# traffic_signals.net
KiCad netlist of a schematic drawn in EAGLE
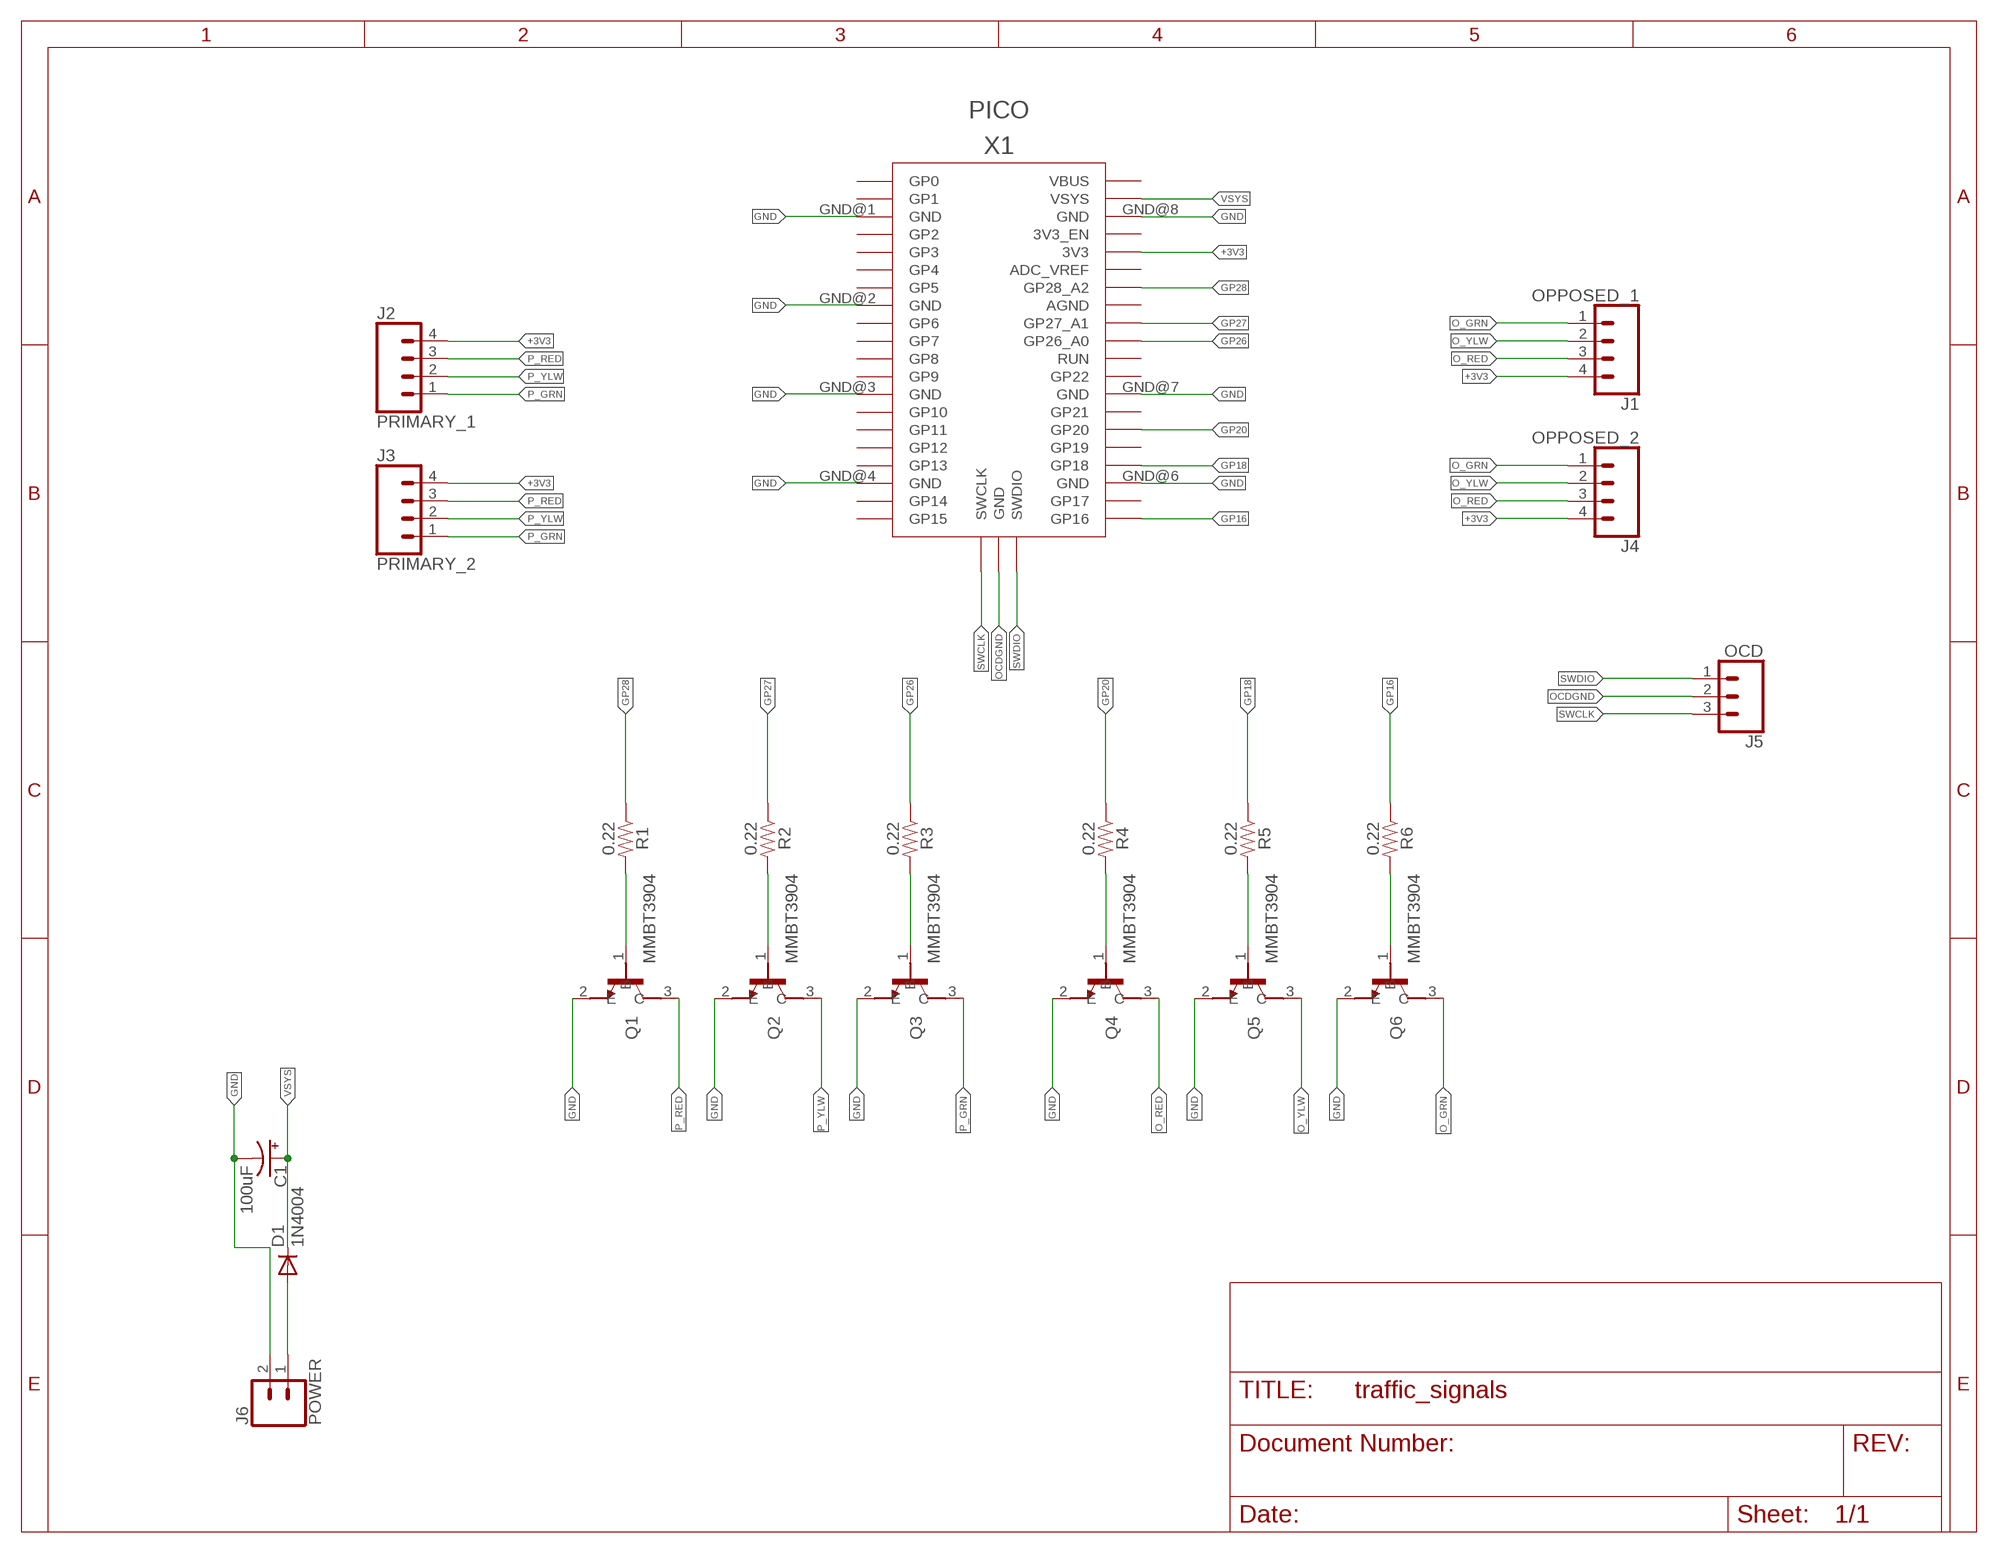
[diagram p0: schematic, sheet 1]

(export (version "E")
  (design (tool "Eeschema 10.0.6"))
  (components
    (comp (ref "C1")
      (value "100uF")
      (footprint "eagle-import:CPOL-RADIAL-2.5MM-6.5MM")
      (libsource (lib "eagle-import") (part "100UF-POLAR-RADIAL-2.5MM-25V-20%"))
    )
    (comp (ref "D1")
      (value "1N4004")
      (footprint "eagle-import:DO41-10")
      (libsource (lib "eagle-import") (part "1N4004"))
    )
    (comp (ref "J1")
      (value "OPPOSED_1")
      (footprint "eagle-import:1X04")
      (libsource (lib "eagle-import") (part "CONN_04"))
    )
    (comp (ref "J2")
      (value "PRIMARY_1")
      (footprint "eagle-import:1X04")
      (libsource (lib "eagle-import") (part "CONN_04"))
    )
    (comp (ref "J3")
      (value "PRIMARY_2")
      (footprint "eagle-import:1X04")
      (libsource (lib "eagle-import") (part "CONN_04"))
    )
    (comp (ref "J4")
      (value "OPPOSED_2")
      (footprint "eagle-import:1X04")
      (libsource (lib "eagle-import") (part "CONN_04"))
    )
    (comp (ref "J5")
      (value "OCD")
      (footprint "eagle-import:1X03")
      (libsource (lib "eagle-import") (part "CONN_03"))
    )
    (comp (ref "J6")
      (value "POWER")
      (footprint "eagle-import:1X02")
      (libsource (lib "eagle-import") (part "CONN_02"))
    )
    (comp (ref "Q1")
      (value "MMBT3904")
      (footprint "eagle-import:SOT95P240X120-3N")
      (fields (field (name "MF") "STMicroelectronics"))
      (libsource (lib "eagle-import") (part "MMBT3904"))
    )
    (comp (ref "Q2")
      (value "MMBT3904")
      (footprint "eagle-import:SOT95P240X120-3N")
      (fields (field (name "MF") "STMicroelectronics"))
      (libsource (lib "eagle-import") (part "MMBT3904"))
    )
    (comp (ref "Q3")
      (value "MMBT3904")
      (footprint "eagle-import:SOT95P240X120-3N")
      (fields (field (name "MF") "STMicroelectronics"))
      (libsource (lib "eagle-import") (part "MMBT3904"))
    )
    (comp (ref "Q4")
      (value "MMBT3904")
      (footprint "eagle-import:SOT95P240X120-3N")
      (fields (field (name "MF") "STMicroelectronics"))
      (libsource (lib "eagle-import") (part "MMBT3904"))
    )
    (comp (ref "Q5")
      (value "MMBT3904")
      (footprint "eagle-import:SOT95P240X120-3N")
      (fields (field (name "MF") "STMicroelectronics"))
      (libsource (lib "eagle-import") (part "MMBT3904"))
    )
    (comp (ref "Q6")
      (value "MMBT3904")
      (footprint "eagle-import:SOT95P240X120-3N")
      (fields (field (name "MF") "STMicroelectronics"))
      (libsource (lib "eagle-import") (part "MMBT3904"))
    )
    (comp (ref "R1")
      (value "0.22")
      (footprint "eagle-import:0805")
      (libsource (lib "eagle-import") (part "0.22OHM-0805-1/4W-1%"))
    )
    (comp (ref "R2")
      (value "0.22")
      (footprint "eagle-import:0805")
      (libsource (lib "eagle-import") (part "0.22OHM-0805-1/4W-1%"))
    )
    (comp (ref "R3")
      (value "0.22")
      (footprint "eagle-import:0805")
      (libsource (lib "eagle-import") (part "0.22OHM-0805-1/4W-1%"))
    )
    (comp (ref "R4")
      (value "0.22")
      (footprint "eagle-import:0805")
      (libsource (lib "eagle-import") (part "0.22OHM-0805-1/4W-1%"))
    )
    (comp (ref "R5")
      (value "0.22")
      (footprint "eagle-import:0805")
      (libsource (lib "eagle-import") (part "0.22OHM-0805-1/4W-1%"))
    )
    (comp (ref "R6")
      (value "0.22")
      (footprint "eagle-import:0805")
      (libsource (lib "eagle-import") (part "0.22OHM-0805-1/4W-1%"))
    )
    (comp (ref "X1")
      (value "PICO")
      (footprint "eagle-import:RPI_PICO_TH")
      (libsource (lib "eagle-import") (part "RPI_PICO_IG-TH"))
    )
  )
  (nets
    (net (code "1") (name "+3V3") (class "Default")
      (node (ref "J1") (pin "4") (pinfunction "4_4") (pintype "passive"))
      (node (ref "J2") (pin "4") (pinfunction "4_4") (pintype "passive"))
      (node (ref "J3") (pin "4") (pinfunction "4_4") (pintype "passive"))
      (node (ref "J4") (pin "4") (pinfunction "4_4") (pintype "passive"))
      (node (ref "X1") (pin "3V3") (pinfunction "3V3_3V3") (pintype "bidirectional"))
    )
    (net (code "2") (name "GND") (class "Default")
      (node (ref "C1") (pin "2") (pinfunction "-_2") (pintype "passive"))
      (node (ref "J6") (pin "2") (pinfunction "2_2") (pintype "passive"))
      (node (ref "Q1") (pin "2") (pinfunction "E_2") (pintype "passive"))
      (node (ref "Q2") (pin "2") (pinfunction "E_2") (pintype "passive"))
      (node (ref "Q3") (pin "2") (pinfunction "E_2") (pintype "passive"))
      (node (ref "Q4") (pin "2") (pinfunction "E_2") (pintype "passive"))
      (node (ref "Q5") (pin "2") (pinfunction "E_2") (pintype "passive"))
      (node (ref "Q6") (pin "2") (pinfunction "E_2") (pintype "passive"))
      (node (ref "X1") (pin "GND@1") (pinfunction "GND_GND@1") (pintype "bidirectional"))
      (node (ref "X1") (pin "GND@2") (pinfunction "GND_GND@2") (pintype "bidirectional"))
      (node (ref "X1") (pin "GND@3") (pinfunction "GND_GND@3") (pintype "bidirectional"))
      (node (ref "X1") (pin "GND@4") (pinfunction "GND_GND@4") (pintype "bidirectional"))
      (node (ref "X1") (pin "GND@6") (pinfunction "GND_GND@6") (pintype "bidirectional"))
      (node (ref "X1") (pin "GND@7") (pinfunction "GND_GND@7") (pintype "bidirectional"))
      (node (ref "X1") (pin "GND@8") (pinfunction "GND_GND@8") (pintype "bidirectional"))
    )
    (net (code "3") (name "GP16") (class "Default")
      (node (ref "R6") (pin "1") (pinfunction "1_1") (pintype "passive"))
      (node (ref "X1") (pin "GP16") (pinfunction "GP16_GP16") (pintype "bidirectional"))
    )
    (net (code "4") (name "GP18") (class "Default")
      (node (ref "R5") (pin "1") (pinfunction "1_1") (pintype "passive"))
      (node (ref "X1") (pin "GP18") (pinfunction "GP18_GP18") (pintype "bidirectional"))
    )
    (net (code "5") (name "GP20") (class "Default")
      (node (ref "R4") (pin "1") (pinfunction "1_1") (pintype "passive"))
      (node (ref "X1") (pin "GP20") (pinfunction "GP20_GP20") (pintype "bidirectional"))
    )
    (net (code "6") (name "GP26") (class "Default")
      (node (ref "R3") (pin "1") (pinfunction "1_1") (pintype "passive"))
      (node (ref "X1") (pin "GP26_A0") (pinfunction "GP26_A0_GP26_A0") (pintype "bidirectional"))
    )
    (net (code "7") (name "GP27") (class "Default")
      (node (ref "R2") (pin "1") (pinfunction "1_1") (pintype "passive"))
      (node (ref "X1") (pin "GP27_A1") (pinfunction "GP27_A1_GP27_A1") (pintype "bidirectional"))
    )
    (net (code "8") (name "GP28") (class "Default")
      (node (ref "R1") (pin "1") (pinfunction "1_1") (pintype "passive"))
      (node (ref "X1") (pin "GP28_A2") (pinfunction "GP28_A2_GP28_A2") (pintype "bidirectional"))
    )
    (net (code "9") (name "Net-(D1-PadA)") (class "Default")
      (node (ref "D1") (pin "A") (pinfunction "A_A") (pintype "passive"))
      (node (ref "J6") (pin "1") (pinfunction "1_1") (pintype "passive"))
    )
    (net (code "10") (name "Net-(Q1-B)") (class "Default")
      (node (ref "Q1") (pin "1") (pinfunction "B_1") (pintype "passive"))
      (node (ref "R1") (pin "2") (pinfunction "2_2") (pintype "passive"))
    )
    (net (code "11") (name "Net-(Q2-B)") (class "Default")
      (node (ref "Q2") (pin "1") (pinfunction "B_1") (pintype "passive"))
      (node (ref "R2") (pin "2") (pinfunction "2_2") (pintype "passive"))
    )
    (net (code "12") (name "Net-(Q3-B)") (class "Default")
      (node (ref "Q3") (pin "1") (pinfunction "B_1") (pintype "passive"))
      (node (ref "R3") (pin "2") (pinfunction "2_2") (pintype "passive"))
    )
    (net (code "13") (name "Net-(Q4-B)") (class "Default")
      (node (ref "Q4") (pin "1") (pinfunction "B_1") (pintype "passive"))
      (node (ref "R4") (pin "2") (pinfunction "2_2") (pintype "passive"))
    )
    (net (code "14") (name "Net-(Q5-B)") (class "Default")
      (node (ref "Q5") (pin "1") (pinfunction "B_1") (pintype "passive"))
      (node (ref "R5") (pin "2") (pinfunction "2_2") (pintype "passive"))
    )
    (net (code "15") (name "Net-(Q6-B)") (class "Default")
      (node (ref "Q6") (pin "1") (pinfunction "B_1") (pintype "passive"))
      (node (ref "R6") (pin "2") (pinfunction "2_2") (pintype "passive"))
    )
    (net (code "16") (name "OCDGND") (class "Default")
      (node (ref "J5") (pin "2") (pinfunction "2_2") (pintype "passive"))
      (node (ref "X1") (pin "GND@5") (pinfunction "GND_GND@5") (pintype "bidirectional"))
    )
    (net (code "17") (name "O_GRN") (class "Default")
      (node (ref "J1") (pin "1") (pinfunction "1_1") (pintype "passive"))
      (node (ref "J4") (pin "1") (pinfunction "1_1") (pintype "passive"))
      (node (ref "Q6") (pin "3") (pinfunction "C_3") (pintype "passive"))
    )
    (net (code "18") (name "O_RED") (class "Default")
      (node (ref "J1") (pin "3") (pinfunction "3_3") (pintype "passive"))
      (node (ref "J4") (pin "3") (pinfunction "3_3") (pintype "passive"))
      (node (ref "Q4") (pin "3") (pinfunction "C_3") (pintype "passive"))
    )
    (net (code "19") (name "O_YLW") (class "Default")
      (node (ref "J1") (pin "2") (pinfunction "2_2") (pintype "passive"))
      (node (ref "J4") (pin "2") (pinfunction "2_2") (pintype "passive"))
      (node (ref "Q5") (pin "3") (pinfunction "C_3") (pintype "passive"))
    )
    (net (code "20") (name "P_GRN") (class "Default")
      (node (ref "J2") (pin "1") (pinfunction "1_1") (pintype "passive"))
      (node (ref "J3") (pin "1") (pinfunction "1_1") (pintype "passive"))
      (node (ref "Q3") (pin "3") (pinfunction "C_3") (pintype "passive"))
    )
    (net (code "21") (name "P_RED") (class "Default")
      (node (ref "J2") (pin "3") (pinfunction "3_3") (pintype "passive"))
      (node (ref "J3") (pin "3") (pinfunction "3_3") (pintype "passive"))
      (node (ref "Q1") (pin "3") (pinfunction "C_3") (pintype "passive"))
    )
    (net (code "22") (name "P_YLW") (class "Default")
      (node (ref "J2") (pin "2") (pinfunction "2_2") (pintype "passive"))
      (node (ref "J3") (pin "2") (pinfunction "2_2") (pintype "passive"))
      (node (ref "Q2") (pin "3") (pinfunction "C_3") (pintype "passive"))
    )
    (net (code "23") (name "SWCLK") (class "Default")
      (node (ref "J5") (pin "3") (pinfunction "3_3") (pintype "passive"))
      (node (ref "X1") (pin "SWCLK") (pinfunction "SWCLK_SWCLK") (pintype "bidirectional"))
    )
    (net (code "24") (name "SWDIO") (class "Default")
      (node (ref "J5") (pin "1") (pinfunction "1_1") (pintype "passive"))
      (node (ref "X1") (pin "SWDIO") (pinfunction "SWDIO_SWDIO") (pintype "bidirectional"))
    )
    (net (code "25") (name "VSYS") (class "Default")
      (node (ref "C1") (pin "1") (pinfunction "+_1") (pintype "passive"))
      (node (ref "D1") (pin "C") (pinfunction "C_C") (pintype "passive"))
      (node (ref "X1") (pin "VSYS") (pinfunction "VSYS_VSYS") (pintype "bidirectional"))
    )
    (net (code "26") (name "unconnected-(X1-Pad3V3_EN)") (class "Default")
      (node (ref "X1") (pin "3V3_EN") (pinfunction "3V3_EN_3V3_EN") (pintype "bidirectional"))
    )
    (net (code "27") (name "unconnected-(X1-PadADC_VREF)") (class "Default")
      (node (ref "X1") (pin "ADC_VREF") (pinfunction "ADC_VREF_ADC_VREF") (pintype "bidirectional"))
    )
    (net (code "28") (name "unconnected-(X1-PadAGND)") (class "Default")
      (node (ref "X1") (pin "AGND") (pinfunction "AGND_AGND") (pintype "bidirectional"))
    )
    (net (code "29") (name "unconnected-(X1-PadGP0)") (class "Default")
      (node (ref "X1") (pin "GP0") (pinfunction "GP0_GP0") (pintype "bidirectional"))
    )
    (net (code "30") (name "unconnected-(X1-PadGP1)") (class "Default")
      (node (ref "X1") (pin "GP1") (pinfunction "GP1_GP1") (pintype "bidirectional"))
    )
    (net (code "31") (name "unconnected-(X1-PadGP2)") (class "Default")
      (node (ref "X1") (pin "GP2") (pinfunction "GP2_GP2") (pintype "bidirectional"))
    )
    (net (code "32") (name "unconnected-(X1-PadGP3)") (class "Default")
      (node (ref "X1") (pin "GP3") (pinfunction "GP3_GP3") (pintype "bidirectional"))
    )
    (net (code "33") (name "unconnected-(X1-PadGP4)") (class "Default")
      (node (ref "X1") (pin "GP4") (pinfunction "GP4_GP4") (pintype "bidirectional"))
    )
    (net (code "34") (name "unconnected-(X1-PadGP5)") (class "Default")
      (node (ref "X1") (pin "GP5") (pinfunction "GP5_GP5") (pintype "bidirectional"))
    )
    (net (code "35") (name "unconnected-(X1-PadGP6)") (class "Default")
      (node (ref "X1") (pin "GP6") (pinfunction "GP6_GP6") (pintype "bidirectional"))
    )
    (net (code "36") (name "unconnected-(X1-PadGP7)") (class "Default")
      (node (ref "X1") (pin "GP7") (pinfunction "GP7_GP7") (pintype "bidirectional"))
    )
    (net (code "37") (name "unconnected-(X1-PadGP8)") (class "Default")
      (node (ref "X1") (pin "GP8") (pinfunction "GP8_GP8") (pintype "bidirectional"))
    )
    (net (code "38") (name "unconnected-(X1-PadGP9)") (class "Default")
      (node (ref "X1") (pin "GP9") (pinfunction "GP9_GP9") (pintype "bidirectional"))
    )
    (net (code "39") (name "unconnected-(X1-PadGP10)") (class "Default")
      (node (ref "X1") (pin "GP10") (pinfunction "GP10_GP10") (pintype "bidirectional"))
    )
    (net (code "40") (name "unconnected-(X1-PadGP11)") (class "Default")
      (node (ref "X1") (pin "GP11") (pinfunction "GP11_GP11") (pintype "bidirectional"))
    )
    (net (code "41") (name "unconnected-(X1-PadGP12)") (class "Default")
      (node (ref "X1") (pin "GP12") (pinfunction "GP12_GP12") (pintype "bidirectional"))
    )
    (net (code "42") (name "unconnected-(X1-PadGP13)") (class "Default")
      (node (ref "X1") (pin "GP13") (pinfunction "GP13_GP13") (pintype "bidirectional"))
    )
    (net (code "43") (name "unconnected-(X1-PadGP14)") (class "Default")
      (node (ref "X1") (pin "GP14") (pinfunction "GP14_GP14") (pintype "bidirectional"))
    )
    (net (code "44") (name "unconnected-(X1-PadGP15)") (class "Default")
      (node (ref "X1") (pin "GP15") (pinfunction "GP15_GP15") (pintype "bidirectional"))
    )
    (net (code "45") (name "unconnected-(X1-PadGP17)") (class "Default")
      (node (ref "X1") (pin "GP17") (pinfunction "GP17_GP17") (pintype "bidirectional"))
    )
    (net (code "46") (name "unconnected-(X1-PadGP19)") (class "Default")
      (node (ref "X1") (pin "GP19") (pinfunction "GP19_GP19") (pintype "bidirectional"))
    )
    (net (code "47") (name "unconnected-(X1-PadGP21)") (class "Default")
      (node (ref "X1") (pin "GP21") (pinfunction "GP21_GP21") (pintype "bidirectional"))
    )
    (net (code "48") (name "unconnected-(X1-PadGP22)") (class "Default")
      (node (ref "X1") (pin "GP22") (pinfunction "GP22_GP22") (pintype "bidirectional"))
    )
    (net (code "49") (name "unconnected-(X1-PadRUN)") (class "Default")
      (node (ref "X1") (pin "RUN") (pinfunction "RUN_RUN") (pintype "bidirectional"))
    )
    (net (code "50") (name "unconnected-(X1-PadVBUS)") (class "Default")
      (node (ref "X1") (pin "VBUS") (pinfunction "VBUS_VBUS") (pintype "bidirectional"))
    )
  )
)
